# PotsDuino.net
KiCad netlist of a schematic drawn in Altium Designer
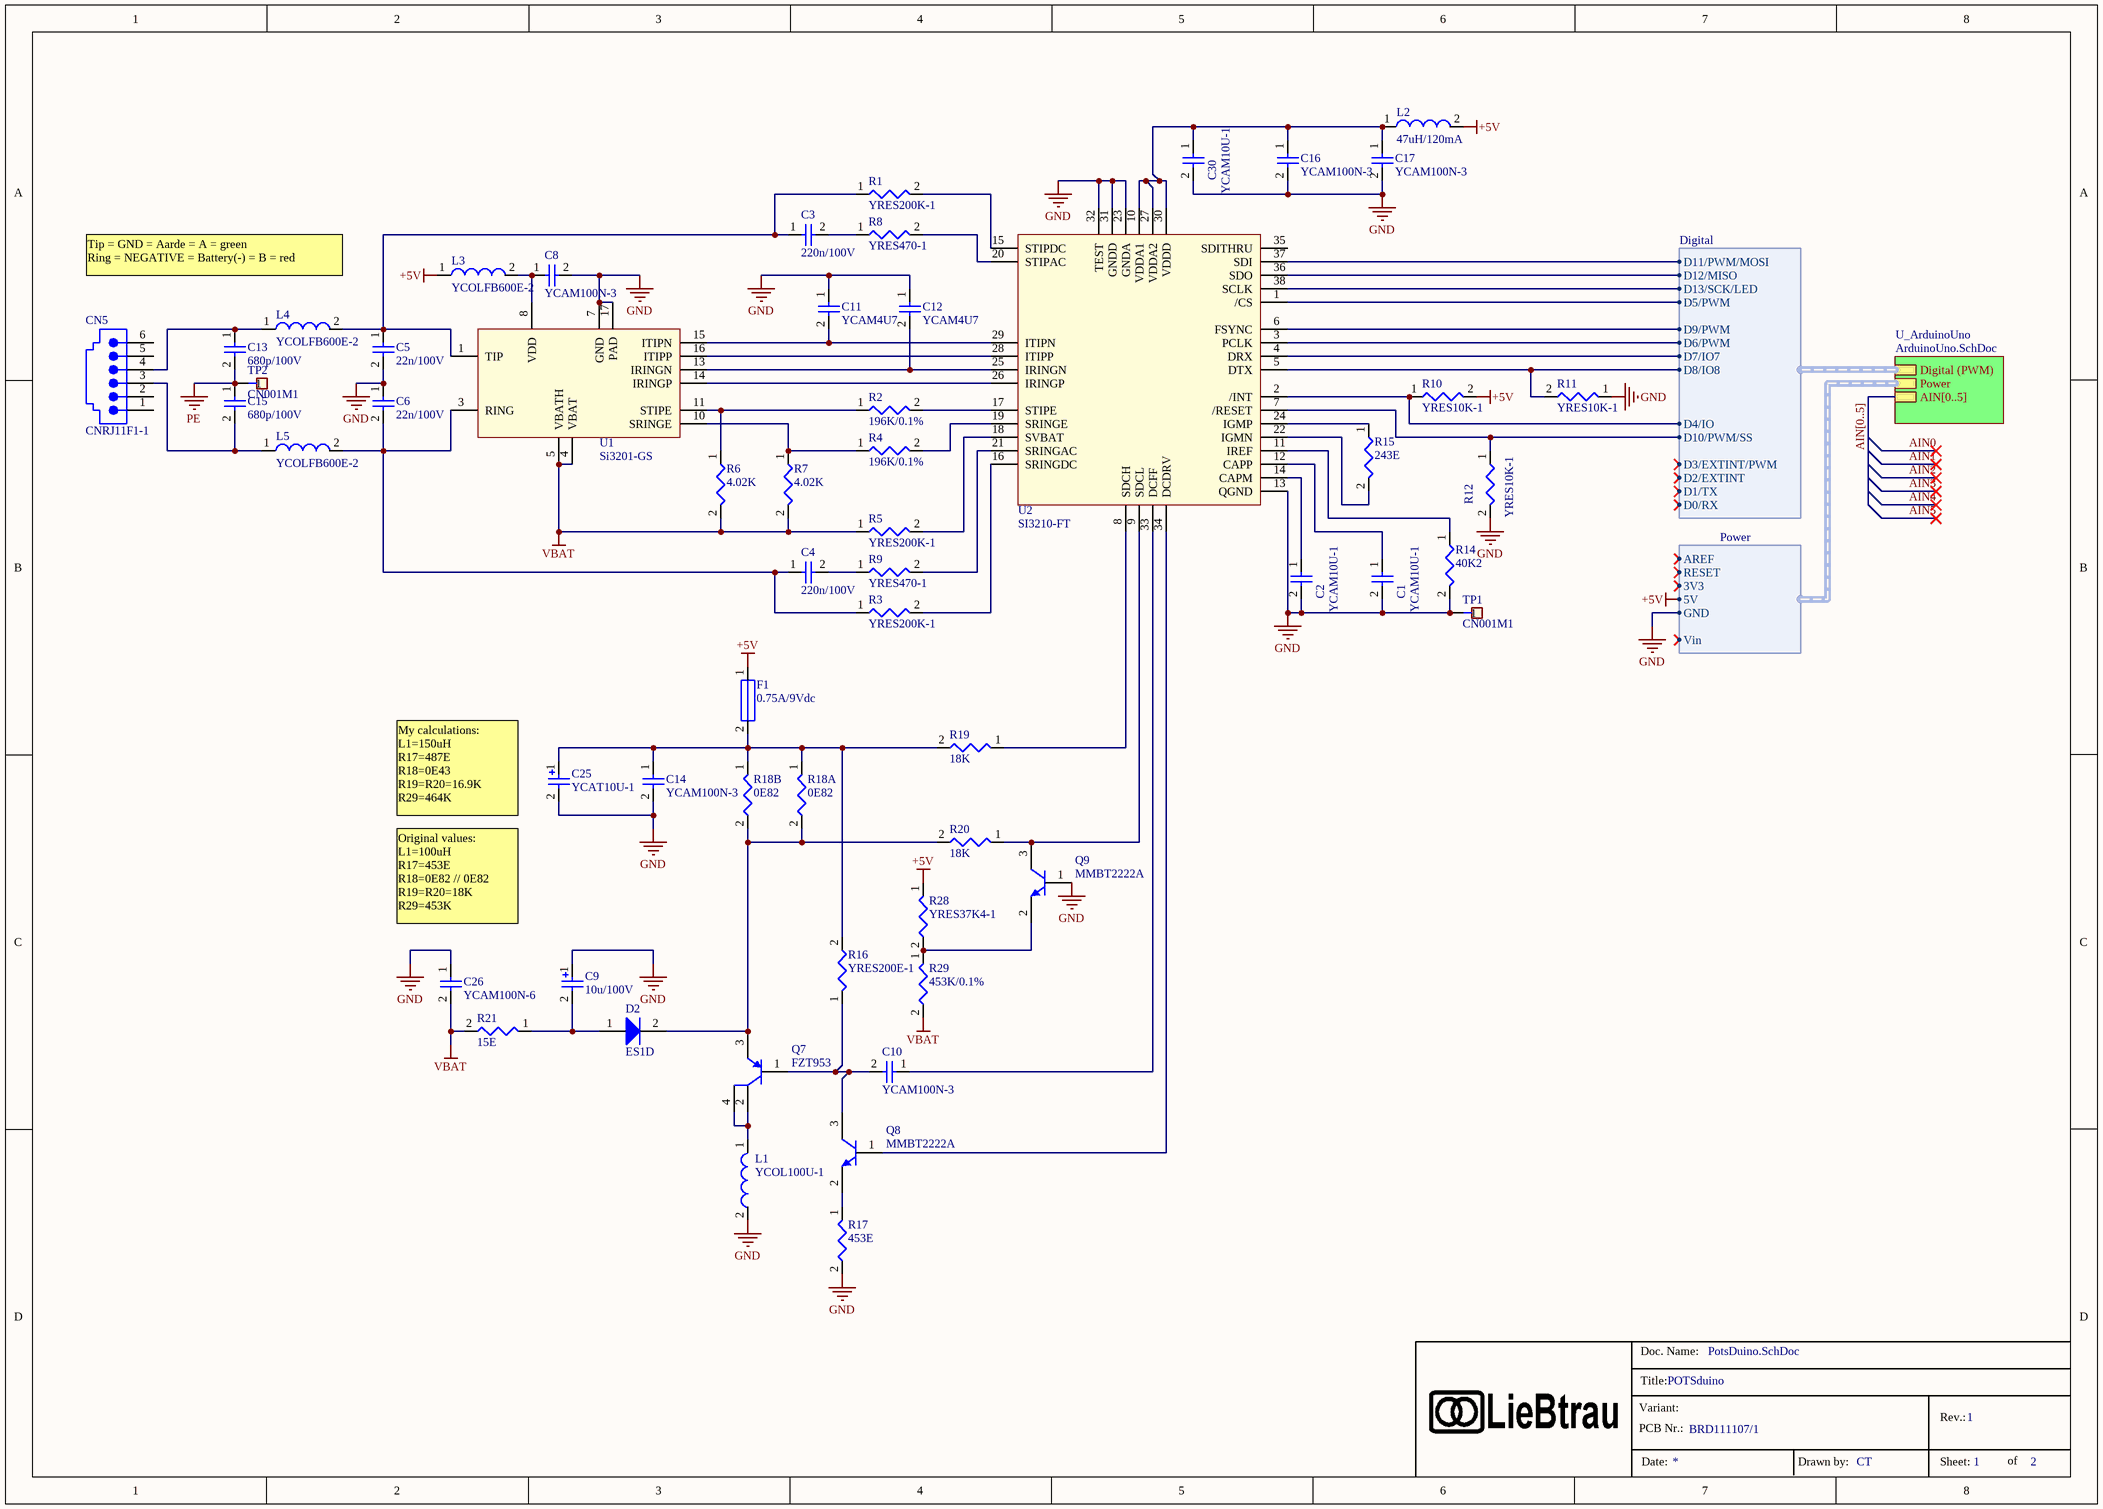
[diagram p0: PotsDuino.SchDoc]

(export (version "E")
  (design (tool "Eeschema 10.0.6"))
  (components
    (comp (ref "C1") (value "YCAM10U-1") (footprint "CA_0805") (libsource (lib "Testing") (part "CA_NONPOL")))
    (comp (ref "C2") (value "YCAM10U-1") (footprint "CA_0805") (libsource (lib "Testing") (part "CA_NONPOL")))
    (comp (ref "C3")
      (value "220n/100V")
      (footprint "CA_0805")
      (fields (field (name "PART NUMBER") "MCCA000493") (field (name "MANUFACTURER") "Multicomp"))
      (libsource (lib "Testing") (part "CA_NONPOL"))
    )
    (comp (ref "C4")
      (value "220n/100V")
      (footprint "CA_0805")
      (fields (field (name "PART NUMBER") "MCCA000493") (field (name "MANUFACTURER") "Multicomp"))
      (libsource (lib "Testing") (part "CA_NONPOL"))
    )
    (comp (ref "C5")
      (value "22n/100V")
      (footprint "CA_0603")
      (fields (field (name "PART NUMBER") "C0603C223K1RACTU") (field (name "MANUFACTURER") "Kemet"))
      (libsource (lib "Testing") (part "CA_NONPOL"))
    )
    (comp (ref "C6")
      (value "22n/100V")
      (footprint "CA_0603")
      (fields (field (name "PART NUMBER") "C0603C223K1RACTU") (field (name "MANUFACTURER") "Kemet"))
      (libsource (lib "Testing") (part "CA_NONPOL"))
    )
    (comp (ref "C8")
      (value "YCAM100N-3")
      (footprint "CA_0603")
      (libsource (lib "Testing") (part "CA_NONPOL"))
    )
    (comp (ref "C9")
      (value "10u/100V")
      (footprint "CA_CANTHD63P25_H110_R")
      (fields (field (name "PART NUMBER") "100YXF10MEFC6.3X11") (field (name "MANUFACTURER") "Rubycon"))
      (libsource (lib "Testing") (part "CA_POL"))
    )
    (comp (ref "C10")
      (value "YCAM100N-3")
      (footprint "CA_0603")
      (libsource (lib "Testing") (part "CA_NONPOL"))
    )
    (comp (ref "C11") (value "YCAM4U7") (footprint "CA_1206") (libsource (lib "Testing") (part "CA_NONPOL")))
    (comp (ref "C12") (value "YCAM4U7") (footprint "CA_1206") (libsource (lib "Testing") (part "CA_NONPOL")))
    (comp (ref "C13")
      (value "680p/100V")
      (footprint "CA_0603")
      (fields (field (name "PART NUMBER") "C0603C681J1GACTU") (field (name "MANUFACTURER") "Kemet"))
      (libsource (lib "Testing") (part "CA_NONPOL"))
    )
    (comp (ref "C14")
      (value "YCAM100N-3")
      (footprint "CA_0603")
      (libsource (lib "Testing") (part "CA_NONPOL"))
    )
    (comp (ref "C15")
      (value "680p/100V")
      (footprint "CA_0603")
      (fields (field (name "PART NUMBER") "C0603C681J1GACTU") (field (name "MANUFACTURER") "Kemet"))
      (libsource (lib "Testing") (part "CA_NONPOL"))
    )
    (comp (ref "C16")
      (value "YCAM100N-3")
      (footprint "CA_0603")
      (libsource (lib "Testing") (part "CA_NONPOL"))
    )
    (comp (ref "C17")
      (value "YCAM100N-3")
      (footprint "CA_0603")
      (libsource (lib "Testing") (part "CA_NONPOL"))
    )
    (comp (ref "C25")
      (value "YCAT10U-1")
      (footprint "CA_1210_H21")
      (libsource (lib "Testing") (part "CA_POL"))
    )
    (comp (ref "C26")
      (value "YCAM100N-6")
      (footprint "CA_0805")
      (libsource (lib "Testing") (part "CA_NONPOL"))
    )
    (comp (ref "C30")
      (value "YCAM10U-1")
      (footprint "CA_0805")
      (libsource (lib "Testing") (part "CA_NONPOL"))
    )
    (comp (ref "CN5")
      (value "CNRJ11F1-1")
      (footprint "CN_MODJACK_6P")
      (libsource (lib "Testing") (part "CN_MODJACK_6P"))
    )
    (comp (ref "D2")
      (value "ES1D")
      (footprint "DI_DO-214AC")
      (description "1 Amp General Purpose Rectifier")
      (fields (field (name "MANUFACTURER") "Fairchild Semiconductor"))
      (libsource (lib "Testing") (part "DI_DIODE"))
    )
    (comp (ref "F1")
      (value "0.75A/9Vdc")
      (footprint "RE_0805")
      (fields (field (name "PART NUMBER") "MC36210") (field (name "MANUFACTURER") "Multicomp"))
      (libsource (lib "Testing") (part "FU_FUSE"))
    )
    (comp (ref "L1")
      (value "YCOL100U-1")
      (footprint "CL_WE-PD4")
      (fields (field (name "MANUFACTURER") "Wuerth Elektronik"))
      (libsource (lib "Testing") (part "CL_COIL"))
    )
    (comp (ref "L2")
      (value "47uH/120mA")
      (footprint "CL_0805")
      (fields (field (name "PART NUMBER") "L0805C470MDWIT") (field (name "MANUFACTURER") "Kemet"))
      (libsource (lib "") (part "CL_COIL_1"))
    )
    (comp (ref "L3")
      (value "YCOLFB600E-2")
      (footprint "CL_0603")
      (fields (field (name "MANUFACTURER") "Murata"))
      (libsource (lib "") (part "CL_COIL_1"))
    )
    (comp (ref "L4")
      (value "YCOLFB600E-2")
      (footprint "CL_0603")
      (fields (field (name "MANUFACTURER") "Murata"))
      (libsource (lib "") (part "CL_COIL_1"))
    )
    (comp (ref "L5")
      (value "YCOLFB600E-2")
      (footprint "CL_0603")
      (fields (field (name "MANUFACTURER") "Murata"))
      (libsource (lib "") (part "CL_COIL_1"))
    )
    (comp (ref "Q7")
      (value "FZT953")
      (footprint "SC_SOT223")
      (description "Amplifier Transistor NPN Silicon")
      (fields (field (name "MANUFACTURER") "Diodes Inc."))
      (libsource (lib "Testing") (part "TR_PNP_1"))
    )
    (comp (ref "Q8")
      (value "MMBT2222A")
      (footprint "SC_SOT23")
      (description "Amplifier Transistor NPN Silicon")
      (fields (field (name "MANUFACTURER") "Fairchild Semiconductor"))
      (libsource (lib "Testing") (part "TR_NPN_1"))
    )
    (comp (ref "Q9")
      (value "MMBT2222A")
      (footprint "SC_SOT23")
      (description "Amplifier Transistor NPN Silicon")
      (fields (field (name "MANUFACTURER") "Fairchild Semiconductor"))
      (libsource (lib "Testing") (part "TR_NPN_1"))
    )
    (comp (ref "R1")
      (value "YRES200K-1")
      (footprint "RE_0603")
      (description "Resistor")
      (libsource (lib "Testing") (part "RE_RES"))
    )
    (comp (ref "R2")
      (value "196K/0.1%")
      (footprint "RE_0603")
      (description "Resistor")
      (fields
        (field (name "PART NUMBER") "ERA3AEB1963V")
        (field (name "MANUFACTURER") "Panasonic Electronic Components")
      )
      (libsource (lib "Testing") (part "RE_RES"))
    )
    (comp (ref "R3")
      (value "YRES200K-1")
      (footprint "RE_0603")
      (description "Resistor")
      (libsource (lib "Testing") (part "RE_RES"))
    )
    (comp (ref "R4")
      (value "196K/0.1%")
      (footprint "RE_0603")
      (description "Resistor")
      (fields
        (field (name "PART NUMBER") "ERA3AEB1963V")
        (field (name "MANUFACTURER") "Panasonic Electronic Components")
      )
      (libsource (lib "Testing") (part "RE_RES"))
    )
    (comp (ref "R5")
      (value "YRES200K-1")
      (footprint "RE_0603")
      (description "Resistor")
      (libsource (lib "Testing") (part "RE_RES"))
    )
    (comp (ref "R6")
      (value "4.02K")
      (footprint "RE_1206")
      (description "Resistor")
      (fields (field (name "PART NUMBER") "CRCW12064K02FKEA") (field (name "MANUFACTURER") "Vishay Draloric"))
      (libsource (lib "Testing") (part "RE_RES"))
    )
    (comp (ref "R7")
      (value "4.02K")
      (footprint "RE_1206")
      (description "Resistor")
      (fields (field (name "PART NUMBER") "CRCW12064K02FKEA") (field (name "MANUFACTURER") "Vishay Draloric"))
      (libsource (lib "Testing") (part "RE_RES"))
    )
    (comp (ref "R8")
      (value "YRES470-1")
      (footprint "RE_0603")
      (description "Resistor")
      (libsource (lib "Testing") (part "RE_RES"))
    )
    (comp (ref "R9")
      (value "YRES470-1")
      (footprint "RE_0603")
      (description "Resistor")
      (libsource (lib "Testing") (part "RE_RES"))
    )
    (comp (ref "R10")
      (value "YRES10K-1")
      (footprint "RE_0603")
      (description "Resistor")
      (libsource (lib "Testing") (part "RE_RES"))
    )
    (comp (ref "R11")
      (value "YRES10K-1")
      (footprint "RE_0603")
      (description "Resistor")
      (libsource (lib "Testing") (part "RE_RES"))
    )
    (comp (ref "R12")
      (value "YRES10K-1")
      (footprint "RE_0603")
      (description "Resistor")
      (libsource (lib "Testing") (part "RE_RES"))
    )
    (comp (ref "R14")
      (value "40K2")
      (footprint "RE_0603")
      (description "Resistor")
      (fields (field (name "PART NUMBER") "MC 0.063W 0603 1% 40K2") (field (name "MANUFACTURER") "Multicomp"))
      (libsource (lib "Testing") (part "RE_RES"))
    )
    (comp (ref "R15")
      (value "243E")
      (footprint "RE_0603")
      (description "Resistor")
      (fields (field (name "PART NUMBER") "MC 0.063W 0603 1% 243R") (field (name "MANUFACTURER") "Multicomp"))
      (libsource (lib "Testing") (part "RE_RES"))
    )
    (comp (ref "R16")
      (value "YRES200E-1")
      (footprint "RE_0603")
      (description "Resistor")
      (libsource (lib "Testing") (part "RE_RES"))
    )
    (comp (ref "R17")
      (value "453E")
      (footprint "RE_0805")
      (description "Resistor")
      (fields (field (name "PART NUMBER") "MCTC0525B4530T5E") (field (name "MANUFACTURER") "Multicomp"))
      (libsource (lib "Testing") (part "RE_RES"))
    )
    (comp (ref "R18A")
      (value "0E82")
      (footprint "RE_0805")
      (description "Resistor")
      (fields
        (field (name "PART NUMBER") "ERJ6RQFR82V")
        (field (name "MANUFACTURER") "Panasonic Electronic Components")
      )
      (libsource (lib "Testing") (part "RE_RES"))
    )
    (comp (ref "R18B")
      (value "0E82")
      (footprint "RE_0805")
      (description "Resistor")
      (fields
        (field (name "PART NUMBER") "ERJ6RQFR82V")
        (field (name "MANUFACTURER") "Panasonic Electronic Components")
      )
      (libsource (lib "Testing") (part "RE_RES"))
    )
    (comp (ref "R19")
      (value "18K")
      (footprint "RE_0603")
      (description "Resistor")
      (fields (field (name "PART NUMBER") "SG73S1JTTD1802F") (field (name "MANUFACTURER") "KOA"))
      (libsource (lib "Testing") (part "RE_RES"))
    )
    (comp (ref "R20")
      (value "18K")
      (footprint "RE_0603")
      (description "Resistor")
      (fields (field (name "PART NUMBER") "SG73S1JTTD1802F") (field (name "MANUFACTURER") "KOA"))
      (libsource (lib "Testing") (part "RE_RES"))
    )
    (comp (ref "R21")
      (value "15E")
      (footprint "RE_0805")
      (description "Resistor")
      (fields (field (name "PART NUMBER") "SG73P2ATTD15R0F") (field (name "MANUFACTURER") "KOA"))
      (libsource (lib "Testing") (part "RE_RES"))
    )
    (comp (ref "R28")
      (value "YRES37K4-1")
      (footprint "RE_0603")
      (description "Resistor")
      (libsource (lib "Testing") (part "RE_RES"))
    )
    (comp (ref "R29")
      (value "453K/0.1%")
      (footprint "RE_0805")
      (description "Resistor")
      (fields (field (name "PART NUMBER") "MCTC0525B4533T5E") (field (name "MANUFACTURER") "Multicomp"))
      (libsource (lib "Testing") (part "RE_RES"))
    )
    (comp (ref "TP1")
      (value "CN001M1")
      (footprint "CN_TP_TH_1.3mm")
      (libsource (lib "Testing") (part "CN_TESTPIN"))
    )
    (comp (ref "TP2")
      (value "CN001M1")
      (footprint "CN_TP_TH_1.3mm")
      (libsource (lib "Testing") (part "CN_TESTPIN"))
    )
    (comp (ref "U1")
      (value "Si3201-GS")
      (footprint "SC_ESOIC16")
      (fields (field (name "MANUFACTURER") "Silicon Labs"))
      (libsource (lib "Testing") (part "IC_Si3201"))
    )
    (comp (ref "U2")
      (value "SI3210-FT")
      (footprint "SC_TSSOP38")
      (fields (field (name "MANUFACTURER") "Silicon Labs"))
      (libsource (lib "Testing") (part "IC_Si3210"))
    )
  )
  (nets
    (net (code "3") (name "+5V") (class "Default")
      (node (ref "F1") (pin "1") (pinfunction "1_1") (pintype "passive"))
      (node (ref "L2") (pin "2") (pinfunction "2_2") (pintype "passive"))
      (node (ref "L3") (pin "1") (pinfunction "1_1") (pintype "passive"))
      (node (ref "R10") (pin "2") (pinfunction "2_2") (pintype "passive"))
      (node (ref "R28") (pin "1") (pinfunction "1_1") (pintype "passive"))
    )
    (net (code "11") (name "/D4{slash}IO") (class "Default")
      (node (ref "R10") (pin "1") (pinfunction "1_1") (pintype "passive"))
      (node (ref "U2") (pin "2") (pinfunction "/INT_2") (pintype "passive"))
    )
    (net (code "12") (name "/D5{slash}PWM") (class "Default")
      (node (ref "U2") (pin "1") (pinfunction "/CS_1") (pintype "passive"))
    )
    (net (code "13") (name "/D6{slash}PWM") (class "Default")
      (node (ref "U2") (pin "3") (pinfunction "PCLK_3") (pintype "passive"))
    )
    (net (code "14") (name "/D7{slash}IO7") (class "Default")
      (node (ref "U2") (pin "4") (pinfunction "DRX_4") (pintype "passive"))
    )
    (net (code "15") (name "/D8{slash}IO8") (class "Default")
      (node (ref "R11") (pin "2") (pinfunction "2_2") (pintype "passive"))
      (node (ref "U2") (pin "5") (pinfunction "DTX_5") (pintype "passive"))
    )
    (net (code "16") (name "/D9{slash}PWM") (class "Default")
      (node (ref "U2") (pin "6") (pinfunction "FSYNC_6") (pintype "passive"))
    )
    (net (code "17") (name "/D10{slash}PWM{slash}SS") (class "Default")
      (node (ref "R12") (pin "1") (pinfunction "1_1") (pintype "passive"))
      (node (ref "U2") (pin "7") (pinfunction "/RESET_7") (pintype "passive"))
    )
    (net (code "18") (name "/D11{slash}PWM{slash}MOSI") (class "Default")
      (node (ref "U2") (pin "37") (pinfunction "SDI_37") (pintype "passive"))
    )
    (net (code "19") (name "/D12{slash}MISO") (class "Default")
      (node (ref "U2") (pin "36") (pinfunction "SDO_36") (pintype "passive"))
    )
    (net (code "20") (name "/D13{slash}SCK{slash}LED") (class "Default")
      (node (ref "U2") (pin "38") (pinfunction "SCLK_38") (pintype "passive"))
    )
    (net (code "23") (name "GND") (class "Default")
      (node (ref "C1") (pin "2") (pinfunction "2_2") (pintype "passive"))
      (node (ref "C11") (pin "1") (pinfunction "1_1") (pintype "passive"))
      (node (ref "C12") (pin "1") (pinfunction "1_1") (pintype "passive"))
      (node (ref "C14") (pin "2") (pinfunction "2_2") (pintype "passive"))
      (node (ref "C16") (pin "2") (pinfunction "2_2") (pintype "passive"))
      (node (ref "C17") (pin "2") (pinfunction "2_2") (pintype "passive"))
      (node (ref "C2") (pin "2") (pinfunction "2_2") (pintype "passive"))
      (node (ref "C25") (pin "2") (pinfunction "2_2") (pintype "passive"))
      (node (ref "C26") (pin "1") (pinfunction "1_1") (pintype "passive"))
      (node (ref "C30") (pin "2") (pinfunction "2_2") (pintype "passive"))
      (node (ref "C5") (pin "2") (pinfunction "2_2") (pintype "passive"))
      (node (ref "C6") (pin "1") (pinfunction "1_1") (pintype "passive"))
      (node (ref "C8") (pin "2") (pinfunction "2_2") (pintype "passive"))
      (node (ref "C9") (pin "1") (pinfunction "1_1") (pintype "passive"))
      (node (ref "L1") (pin "2") (pinfunction "2_2") (pintype "passive"))
      (node (ref "Q9") (pin "1") (pinfunction "C_1") (pintype "passive"))
      (node (ref "R11") (pin "1") (pinfunction "1_1") (pintype "passive"))
      (node (ref "R12") (pin "2") (pinfunction "2_2") (pintype "passive"))
      (node (ref "R14") (pin "2") (pinfunction "2_2") (pintype "passive"))
      (node (ref "R17") (pin "2") (pinfunction "2_2") (pintype "passive"))
      (node (ref "TP1") (pin "1") (pinfunction "1_1") (pintype "passive"))
      (node (ref "U1") (pin "17") (pinfunction "PAD_17") (pintype "passive"))
      (node (ref "U1") (pin "7") (pinfunction "GND_7") (pintype "passive"))
      (node (ref "U2") (pin "13") (pinfunction "QGND_13") (pintype "passive"))
      (node (ref "U2") (pin "23") (pinfunction "GNDA_23") (pintype "passive"))
      (node (ref "U2") (pin "31") (pinfunction "GNDD_31") (pintype "passive"))
      (node (ref "U2") (pin "32") (pinfunction "TEST_32") (pintype "passive"))
    )
    (net (code "24") (name "Net-(C3-Pad2)") (class "Default")
      (node (ref "C3") (pin "2") (pinfunction "2_2") (pintype "passive"))
      (node (ref "R8") (pin "1") (pinfunction "1_1") (pintype "passive"))
    )
    (net (code "25") (name "Net-(C4-Pad2)") (class "Default")
      (node (ref "C4") (pin "2") (pinfunction "2_2") (pintype "passive"))
      (node (ref "R9") (pin "1") (pinfunction "1_1") (pintype "passive"))
    )
    (net (code "26") (name "Net-(C13-Pad1)") (class "Default")
      (node (ref "C13") (pin "1") (pinfunction "1_1") (pintype "passive"))
      (node (ref "CN5") (pin "4") (pinfunction "4_4") (pintype "passive"))
      (node (ref "L4") (pin "1") (pinfunction "1_1") (pintype "passive"))
    )
    (net (code "27") (name "Net-(C14-Pad1)") (class "Default")
      (node (ref "C14") (pin "1") (pinfunction "1_1") (pintype "passive"))
      (node (ref "C25") (pin "1") (pinfunction "1_1") (pintype "passive"))
      (node (ref "F1") (pin "2") (pinfunction "2_2") (pintype "passive"))
      (node (ref "R16") (pin "2") (pinfunction "2_2") (pintype "passive"))
      (node (ref "R18A") (pin "1") (pinfunction "1_1") (pintype "passive"))
      (node (ref "R18B") (pin "1") (pinfunction "1_1") (pintype "passive"))
      (node (ref "R19") (pin "2") (pinfunction "2_2") (pintype "passive"))
    )
    (net (code "28") (name "Net-(C15-Pad2)") (class "Default")
      (node (ref "C15") (pin "2") (pinfunction "2_2") (pintype "passive"))
      (node (ref "CN5") (pin "3") (pinfunction "3_3") (pintype "passive"))
      (node (ref "L5") (pin "1") (pinfunction "1_1") (pintype "passive"))
    )
    (net (code "29") (name "Net-(D2-A)") (class "Default")
      (node (ref "C9") (pin "2") (pinfunction "2_2") (pintype "passive"))
      (node (ref "D2") (pin "1") (pinfunction "A_1") (pintype "passive"))
      (node (ref "R21") (pin "1") (pinfunction "1_1") (pintype "passive"))
    )
    (net (code "30") (name "Net-(D2-K)") (class "Default")
      (node (ref "D2") (pin "2") (pinfunction "K_2") (pintype "passive"))
      (node (ref "Q7") (pin "3") (pinfunction "E_3") (pintype "passive"))
      (node (ref "R18A") (pin "2") (pinfunction "2_2") (pintype "passive"))
      (node (ref "R18B") (pin "2") (pinfunction "2_2") (pintype "passive"))
      (node (ref "R20") (pin "2") (pinfunction "2_2") (pintype "passive"))
    )
    (net (code "31") (name "Net-(Q7-B)") (class "Default")
      (node (ref "L1") (pin "1") (pinfunction "1_1") (pintype "passive"))
      (node (ref "Q7") (pin "2") (pinfunction "B_2") (pintype "passive"))
      (node (ref "Q7") (pin "4") (pinfunction "4_4") (pintype "passive"))
    )
    (net (code "32") (name "Net-(Q7-C)") (class "Default")
      (node (ref "C10") (pin "2") (pinfunction "2_2") (pintype "passive"))
      (node (ref "Q7") (pin "1") (pinfunction "C_1") (pintype "passive"))
      (node (ref "Q8") (pin "3") (pinfunction "E_3") (pintype "passive"))
      (node (ref "R16") (pin "1") (pinfunction "1_1") (pintype "passive"))
    )
    (net (code "33") (name "Net-(Q8-B)") (class "Default")
      (node (ref "Q8") (pin "2") (pinfunction "B_2") (pintype "passive"))
      (node (ref "R17") (pin "1") (pinfunction "1_1") (pintype "passive"))
    )
    (net (code "34") (name "Net-(Q8-C)") (class "Default")
      (node (ref "Q8") (pin "1") (pinfunction "C_1") (pintype "passive"))
      (node (ref "U2") (pin "34") (pinfunction "DCDRV_34") (pintype "passive"))
    )
    (net (code "35") (name "Net-(Q9-B)") (class "Default")
      (node (ref "Q9") (pin "2") (pinfunction "B_2") (pintype "passive"))
      (node (ref "R28") (pin "2") (pinfunction "2_2") (pintype "passive"))
      (node (ref "R29") (pin "1") (pinfunction "1_1") (pintype "passive"))
    )
    (net (code "36") (name "Net-(Q9-E)") (class "Default")
      (node (ref "Q9") (pin "3") (pinfunction "E_3") (pintype "passive"))
      (node (ref "R20") (pin "1") (pinfunction "1_1") (pintype "passive"))
      (node (ref "U2") (pin "9") (pinfunction "SDCL_9") (pintype "passive"))
    )
    (net (code "37") (name "Net-(U1-IRINGN)") (class "Default")
      (node (ref "C12") (pin "2") (pinfunction "2_2") (pintype "passive"))
      (node (ref "U1") (pin "13") (pinfunction "IRINGN_13") (pintype "passive"))
      (node (ref "U2") (pin "25") (pinfunction "IRINGN_25") (pintype "passive"))
    )
    (net (code "38") (name "Net-(U1-IRINGP)") (class "Default")
      (node (ref "U1") (pin "14") (pinfunction "IRINGP_14") (pintype "passive"))
      (node (ref "U2") (pin "26") (pinfunction "IRINGP_26") (pintype "passive"))
    )
    (net (code "39") (name "Net-(U1-ITIPN)") (class "Default")
      (node (ref "C11") (pin "2") (pinfunction "2_2") (pintype "passive"))
      (node (ref "U1") (pin "15") (pinfunction "ITIPN_15") (pintype "passive"))
      (node (ref "U2") (pin "29") (pinfunction "ITIPN_29") (pintype "passive"))
    )
    (net (code "40") (name "Net-(U1-ITIPP)") (class "Default")
      (node (ref "U1") (pin "16") (pinfunction "ITIPP_16") (pintype "passive"))
      (node (ref "U2") (pin "28") (pinfunction "ITIPP_28") (pintype "passive"))
    )
    (net (code "41") (name "Net-(U1-RING)") (class "Default")
      (node (ref "C4") (pin "1") (pinfunction "1_1") (pintype "passive"))
      (node (ref "C6") (pin "2") (pinfunction "2_2") (pintype "passive"))
      (node (ref "L5") (pin "2") (pinfunction "2_2") (pintype "passive"))
      (node (ref "R3") (pin "1") (pinfunction "1_1") (pintype "passive"))
      (node (ref "U1") (pin "3") (pinfunction "RING_3") (pintype "passive"))
    )
    (net (code "42") (name "Net-(U1-SRINGE)") (class "Default")
      (node (ref "R4") (pin "1") (pinfunction "1_1") (pintype "passive"))
      (node (ref "R7") (pin "1") (pinfunction "1_1") (pintype "passive"))
      (node (ref "U1") (pin "10") (pinfunction "SRINGE_10") (pintype "passive"))
    )
    (net (code "43") (name "Net-(U1-STIPE)") (class "Default")
      (node (ref "R2") (pin "1") (pinfunction "1_1") (pintype "passive"))
      (node (ref "R6") (pin "1") (pinfunction "1_1") (pintype "passive"))
      (node (ref "U1") (pin "11") (pinfunction "STIPE_11") (pintype "passive"))
    )
    (net (code "44") (name "Net-(U1-TIP)") (class "Default")
      (node (ref "C3") (pin "1") (pinfunction "1_1") (pintype "passive"))
      (node (ref "C5") (pin "1") (pinfunction "1_1") (pintype "passive"))
      (node (ref "L4") (pin "2") (pinfunction "2_2") (pintype "passive"))
      (node (ref "R1") (pin "1") (pinfunction "1_1") (pintype "passive"))
      (node (ref "U1") (pin "1") (pinfunction "TIP_1") (pintype "passive"))
    )
    (net (code "45") (name "Net-(U1-VDD)") (class "Default")
      (node (ref "C8") (pin "1") (pinfunction "1_1") (pintype "passive"))
      (node (ref "L3") (pin "2") (pinfunction "2_2") (pintype "passive"))
      (node (ref "U1") (pin "8") (pinfunction "VDD_8") (pintype "passive"))
    )
    (net (code "46") (name "Net-(U2-CAPM)") (class "Default")
      (node (ref "C2") (pin "1") (pinfunction "1_1") (pintype "passive"))
      (node (ref "U2") (pin "14") (pinfunction "CAPM_14") (pintype "passive"))
    )
    (net (code "47") (name "Net-(U2-CAPP)") (class "Default")
      (node (ref "C1") (pin "1") (pinfunction "1_1") (pintype "passive"))
      (node (ref "U2") (pin "12") (pinfunction "CAPP_12") (pintype "passive"))
    )
    (net (code "48") (name "Net-(U2-DCFF)") (class "Default")
      (node (ref "C10") (pin "1") (pinfunction "1_1") (pintype "passive"))
      (node (ref "U2") (pin "33") (pinfunction "DCFF_33") (pintype "passive"))
    )
    (net (code "49") (name "Net-(U2-IGMN)") (class "Default")
      (node (ref "R15") (pin "2") (pinfunction "2_2") (pintype "passive"))
      (node (ref "U2") (pin "22") (pinfunction "IGMN_22") (pintype "passive"))
    )
    (net (code "50") (name "Net-(U2-IGMP)") (class "Default")
      (node (ref "R15") (pin "1") (pinfunction "1_1") (pintype "passive"))
      (node (ref "U2") (pin "24") (pinfunction "IGMP_24") (pintype "passive"))
    )
    (net (code "51") (name "Net-(U2-IREF)") (class "Default")
      (node (ref "R14") (pin "1") (pinfunction "1_1") (pintype "passive"))
      (node (ref "U2") (pin "11") (pinfunction "IREF_11") (pintype "passive"))
    )
    (net (code "52") (name "Net-(U2-SDCH)") (class "Default")
      (node (ref "R19") (pin "1") (pinfunction "1_1") (pintype "passive"))
      (node (ref "U2") (pin "8") (pinfunction "SDCH_8") (pintype "passive"))
    )
    (net (code "53") (name "Net-(U2-SRINGAC)") (class "Default")
      (node (ref "R9") (pin "2") (pinfunction "2_2") (pintype "passive"))
      (node (ref "U2") (pin "21") (pinfunction "SRINGAC_21") (pintype "passive"))
    )
    (net (code "54") (name "Net-(U2-SRINGDC)") (class "Default")
      (node (ref "R3") (pin "2") (pinfunction "2_2") (pintype "passive"))
      (node (ref "U2") (pin "16") (pinfunction "SRINGDC_16") (pintype "passive"))
    )
    (net (code "55") (name "Net-(U2-SRINGE)") (class "Default")
      (node (ref "R4") (pin "2") (pinfunction "2_2") (pintype "passive"))
      (node (ref "U2") (pin "19") (pinfunction "SRINGE_19") (pintype "passive"))
    )
    (net (code "56") (name "Net-(U2-STIPAC)") (class "Default")
      (node (ref "R8") (pin "2") (pinfunction "2_2") (pintype "passive"))
      (node (ref "U2") (pin "20") (pinfunction "STIPAC_20") (pintype "passive"))
    )
    (net (code "57") (name "Net-(U2-STIPDC)") (class "Default")
      (node (ref "R1") (pin "2") (pinfunction "2_2") (pintype "passive"))
      (node (ref "U2") (pin "15") (pinfunction "STIPDC_15") (pintype "passive"))
    )
    (net (code "58") (name "Net-(U2-STIPE)") (class "Default")
      (node (ref "R2") (pin "2") (pinfunction "2_2") (pintype "passive"))
      (node (ref "U2") (pin "17") (pinfunction "STIPE_17") (pintype "passive"))
    )
    (net (code "59") (name "Net-(U2-SVBAT)") (class "Default")
      (node (ref "R5") (pin "2") (pinfunction "2_2") (pintype "passive"))
      (node (ref "U2") (pin "18") (pinfunction "SVBAT_18") (pintype "passive"))
    )
    (net (code "60") (name "Net-(U2-VDDA1)") (class "Default")
      (node (ref "C16") (pin "1") (pinfunction "1_1") (pintype "passive"))
      (node (ref "C17") (pin "1") (pinfunction "1_1") (pintype "passive"))
      (node (ref "C30") (pin "1") (pinfunction "1_1") (pintype "passive"))
      (node (ref "L2") (pin "1") (pinfunction "1_1") (pintype "passive"))
      (node (ref "U2") (pin "10") (pinfunction "VDDA1_10") (pintype "passive"))
      (node (ref "U2") (pin "27") (pinfunction "VDDA2_27") (pintype "passive"))
      (node (ref "U2") (pin "30") (pinfunction "VDDD_30") (pintype "passive"))
    )
    (net (code "61") (name "PE") (class "Default")
      (node (ref "C13") (pin "2") (pinfunction "2_2") (pintype "passive"))
      (node (ref "C15") (pin "1") (pinfunction "1_1") (pintype "passive"))
      (node (ref "TP2") (pin "1") (pinfunction "1_1") (pintype "passive"))
    )
    (net (code "62") (name "VBAT") (class "Default")
      (node (ref "C26") (pin "2") (pinfunction "2_2") (pintype "passive"))
      (node (ref "R21") (pin "2") (pinfunction "2_2") (pintype "passive"))
      (node (ref "R29") (pin "2") (pinfunction "2_2") (pintype "passive"))
      (node (ref "R5") (pin "1") (pinfunction "1_1") (pintype "passive"))
      (node (ref "R6") (pin "2") (pinfunction "2_2") (pintype "passive"))
      (node (ref "R7") (pin "2") (pinfunction "2_2") (pintype "passive"))
      (node (ref "U1") (pin "4") (pinfunction "VBAT_4") (pintype "passive"))
      (node (ref "U1") (pin "5") (pinfunction "VBATH_5") (pintype "passive"))
    )
    (net (code "63") (name "unconnected-(CN5-Pad1)") (class "Default")
      (node (ref "CN5") (pin "1") (pinfunction "1_1") (pintype "passive"))
    )
    (net (code "64") (name "unconnected-(CN5-Pad2)") (class "Default")
      (node (ref "CN5") (pin "2") (pinfunction "2_2") (pintype "passive"))
    )
    (net (code "65") (name "unconnected-(CN5-Pad5)") (class "Default")
      (node (ref "CN5") (pin "5") (pinfunction "5_5") (pintype "passive"))
    )
    (net (code "66") (name "unconnected-(CN5-Pad6)") (class "Default")
      (node (ref "CN5") (pin "6") (pinfunction "6_6") (pintype "passive"))
    )
    (net (code "67") (name "unconnected-(U2-SDITHRU-Pad35)") (class "Default")
      (node (ref "U2") (pin "35") (pinfunction "SDITHRU_35") (pintype "passive"))
    )
  )
)
